# untitled.net
KiCad netlist of a schematic drawn in EAGLE
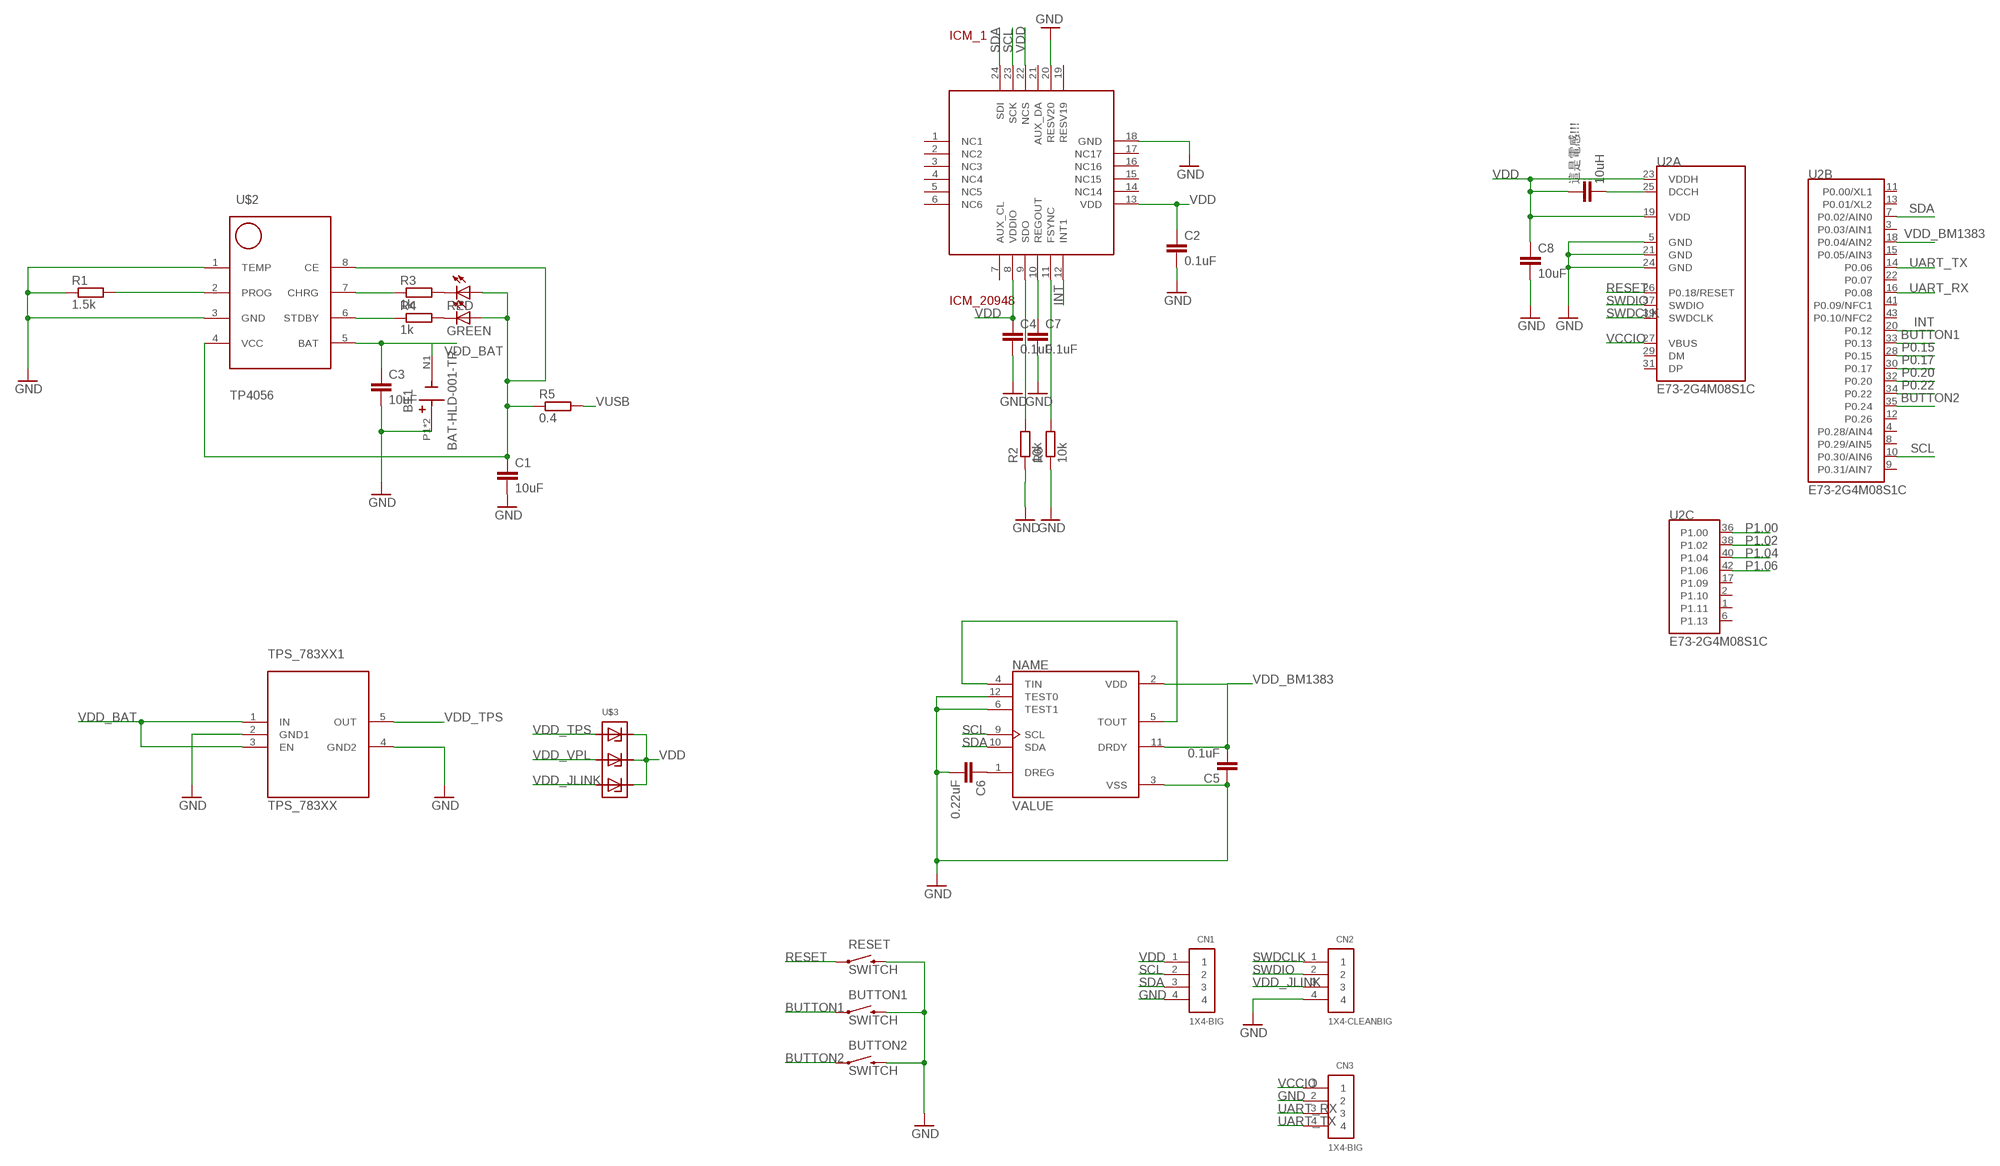
[diagram p0: schematic, sheet 1]

(export (version "E")
  (design (tool "Eeschema 10.0.6"))
  (components
    (comp (ref "BT1")
      (value "BAT-HLD-001-TR")
      (footprint "eagle-import:BAT_BAT-HLD-001-TR")
      (fields (field (name "MF") "Linx"))
      (libsource (lib "eagle-import") (part "BAT-HLD-001-TR"))
    )
    (comp (ref "BUTTON1")
      (value "SWITCH")
      (footprint "eagle-import:SWITCH_2PIN")
      (libsource (lib "eagle-import") (part "SWITCH"))
    )
    (comp (ref "BUTTON2")
      (value "SWITCH")
      (footprint "eagle-import:SWITCH_2PIN")
      (libsource (lib "eagle-import") (part "SWITCH"))
    )
    (comp (ref "C1")
      (value "10uF")
      (footprint "eagle-import:C0805")
      (libsource (lib "eagle-import") (part "C-EUC0805"))
    )
    (comp (ref "C2")
      (value "0.1uF")
      (footprint "eagle-import:C0805")
      (libsource (lib "eagle-import") (part "C-EUC0805"))
    )
    (comp (ref "C3")
      (value "10uF")
      (footprint "eagle-import:C0805")
      (libsource (lib "eagle-import") (part "C-EUC0805"))
    )
    (comp (ref "C4")
      (value "0.1uF")
      (footprint "eagle-import:C0805")
      (libsource (lib "eagle-import") (part "C-EUC0805"))
    )
    (comp (ref "C5")
      (value "0.1uF")
      (footprint "eagle-import:C0805")
      (libsource (lib "eagle-import") (part "C-EUC0805"))
    )
    (comp (ref "C6")
      (value "0.22uF")
      (footprint "eagle-import:C0805")
      (libsource (lib "eagle-import") (part "C-EUC0805"))
    )
    (comp (ref "C7")
      (value "0.1uF")
      (footprint "eagle-import:C0805")
      (libsource (lib "eagle-import") (part "C-EUC0805"))
    )
    (comp (ref "C8")
      (value "10uF")
      (footprint "eagle-import:C0805")
      (libsource (lib "eagle-import") (part "C-EUC0805"))
    )
    (comp (ref "CN1")
      (value "1X4-BIG")
      (footprint "eagle-import:1X04-BIG")
      (libsource (lib "eagle-import") (part "1X4-BIG"))
    )
    (comp (ref "CN2")
      (value "1X4-CLEANBIG")
      (footprint "eagle-import:1X04-CLEANBIG")
      (libsource (lib "eagle-import") (part "1X4-CLEANBIG"))
    )
    (comp (ref "CN3")
      (value "1X4-BIG")
      (footprint "eagle-import:1X04-BIG")
      (libsource (lib "eagle-import") (part "1X4-BIG"))
    )
    (comp (ref "GREEN")
      (value "LED_E")
      (footprint "eagle-import:LED_1206")
      (libsource (lib "eagle-import") (part "LED_E"))
    )
    (comp (ref "ICM_1")
      (value "ICM_20948")
      (footprint "eagle-import:QFN40P300X300X105-25N")
      (libsource (lib "eagle-import") (part "ICM_20948"))
    )
    (comp (ref "R1")
      (value "1.5k")
      (footprint "eagle-import:R0805")
      (libsource (lib "eagle-import") (part "R"))
    )
    (comp (ref "R2")
      (value "10k")
      (footprint "eagle-import:R0805")
      (libsource (lib "eagle-import") (part "R"))
    )
    (comp (ref "R3")
      (value "1k")
      (footprint "eagle-import:R0805")
      (libsource (lib "eagle-import") (part "R"))
    )
    (comp (ref "R4")
      (value "1k")
      (footprint "eagle-import:R0805")
      (libsource (lib "eagle-import") (part "R"))
    )
    (comp (ref "R5")
      (value "0.4")
      (footprint "eagle-import:R0805")
      (libsource (lib "eagle-import") (part "R"))
    )
    (comp (ref "R6")
      (value "10k")
      (footprint "eagle-import:R0805")
      (libsource (lib "eagle-import") (part "R"))
    )
    (comp (ref "RED")
      (value "LED_E")
      (footprint "eagle-import:LED_1206")
      (libsource (lib "eagle-import") (part "LED_E"))
    )
    (comp (ref "RESET")
      (value "SWITCH")
      (footprint "eagle-import:SWITCH_2PIN")
      (libsource (lib "eagle-import") (part "SWITCH"))
    )
    (comp (ref "TPS_783XX1")
      (value "TPS_783XX")
      (footprint "eagle-import:SOT65P280X145-5N")
      (libsource (lib "eagle-import") (part "TPS_783XX"))
    )
    (comp (ref "U$2")
      (value "TP4056")
      (footprint "eagle-import:SOP8")
      (libsource (lib "eagle-import") (part "TP4056"))
    )
    (comp (ref "U$3")
      (value "SD103ATW")
      (footprint "eagle-import:SOT363")
      (libsource (lib "eagle-import") (part "SD103ATW"))
    )
    (comp (ref "U1")
      (value "BM1383AGLV-ZE2")
      (footprint "eagle-import:PQFN55P250X250X100-12N")
      (fields (field (name "MF") "Rohm"))
      (libsource (lib "eagle-import") (part "BM1383AGLV-ZE2"))
    )
    (comp (ref "U2")
      (value "E73-2G4M08S1C")
      (footprint "eagle-import:E73-2G4M08S1C")
      (libsource (lib "eagle-import") (part "E73-2G4M08S1C"))
    )
    (comp (ref "這是電感!!!")
      (value "10uH")
      (footprint "eagle-import:C0805")
      (libsource (lib "eagle-import") (part "C-EUC0805"))
    )
  )
  (nets
    (net (code "1") (name "/BUTTON1") (class "Default")
      (node (ref "BUTTON1") (pin "1") (pinfunction "1_1") (pintype "passive"))
      (node (ref "U2") (pin "33") (pinfunction "P0.13_33") (pintype "bidirectional"))
    )
    (net (code "2") (name "/BUTTON2") (class "Default")
      (node (ref "BUTTON2") (pin "1") (pinfunction "1_1") (pintype "passive"))
      (node (ref "U2") (pin "35") (pinfunction "P0.24_35") (pintype "bidirectional"))
    )
    (net (code "3") (name "/INT") (class "Default")
      (node (ref "ICM_1") (pin "12") (pinfunction "INT1_12") (pintype "bidirectional"))
      (node (ref "U2") (pin "20") (pinfunction "P0.12_20") (pintype "bidirectional"))
    )
    (net (code "4") (name "/P0.15") (class "Default")
      (node (ref "U2") (pin "28") (pinfunction "P0.15_28") (pintype "bidirectional"))
    )
    (net (code "5") (name "/P0.17") (class "Default")
      (node (ref "U2") (pin "30") (pinfunction "P0.17_30") (pintype "bidirectional"))
    )
    (net (code "6") (name "/P0.20") (class "Default")
      (node (ref "U2") (pin "32") (pinfunction "P0.20_32") (pintype "bidirectional"))
    )
    (net (code "7") (name "/P0.22") (class "Default")
      (node (ref "U2") (pin "34") (pinfunction "P0.22_34") (pintype "bidirectional"))
    )
    (net (code "8") (name "/P1.00") (class "Default")
      (node (ref "U2") (pin "36") (pinfunction "P1.00_36") (pintype "bidirectional"))
    )
    (net (code "9") (name "/P1.02") (class "Default")
      (node (ref "U2") (pin "38") (pinfunction "P1.02_38") (pintype "bidirectional"))
    )
    (net (code "10") (name "/P1.04") (class "Default")
      (node (ref "U2") (pin "40") (pinfunction "P1.04_40") (pintype "bidirectional"))
    )
    (net (code "11") (name "/P1.06") (class "Default")
      (node (ref "U2") (pin "42") (pinfunction "P1.06_42") (pintype "bidirectional"))
    )
    (net (code "12") (name "/RESET") (class "Default")
      (node (ref "RESET") (pin "1") (pinfunction "1_1") (pintype "passive"))
      (node (ref "U2") (pin "26") (pinfunction "P0.18/RESET_26") (pintype "bidirectional"))
    )
    (net (code "13") (name "/SCL") (class "Default")
      (node (ref "CN1") (pin "2") (pinfunction "2_2") (pintype "bidirectional"))
      (node (ref "ICM_1") (pin "23") (pinfunction "SCK_23") (pintype "bidirectional"))
      (node (ref "U1") (pin "9") (pinfunction "SCL_9") (pintype "input"))
      (node (ref "U2") (pin "10") (pinfunction "P0.30/AIN6_10") (pintype "bidirectional"))
    )
    (net (code "14") (name "/SDA") (class "Default")
      (node (ref "CN1") (pin "3") (pinfunction "3_3") (pintype "bidirectional"))
      (node (ref "ICM_1") (pin "24") (pinfunction "SDI_24") (pintype "bidirectional"))
      (node (ref "U1") (pin "10") (pinfunction "SDA_10") (pintype "bidirectional"))
      (node (ref "U2") (pin "7") (pinfunction "P0.02/AIN0_7") (pintype "bidirectional"))
    )
    (net (code "15") (name "/SWDCLK") (class "Default")
      (node (ref "CN2") (pin "1") (pinfunction "1_1") (pintype "bidirectional"))
      (node (ref "U2") (pin "39") (pinfunction "SWDCLK_39") (pintype "bidirectional"))
    )
    (net (code "16") (name "/SWDIO") (class "Default")
      (node (ref "CN2") (pin "2") (pinfunction "2_2") (pintype "bidirectional"))
      (node (ref "U2") (pin "37") (pinfunction "SWDIO_37") (pintype "bidirectional"))
    )
    (net (code "17") (name "/UART_RX") (class "Default")
      (node (ref "CN3") (pin "3") (pinfunction "3_3") (pintype "bidirectional"))
      (node (ref "U2") (pin "16") (pinfunction "P0.08_16") (pintype "bidirectional"))
    )
    (net (code "18") (name "/UART_TX") (class "Default")
      (node (ref "CN3") (pin "4") (pinfunction "4_4") (pintype "bidirectional"))
      (node (ref "U2") (pin "14") (pinfunction "P0.06_14") (pintype "bidirectional"))
    )
    (net (code "19") (name "/VCCIO") (class "Default")
      (node (ref "CN3") (pin "1") (pinfunction "1_1") (pintype "bidirectional"))
      (node (ref "U2") (pin "27") (pinfunction "VBUS_27") (pintype "bidirectional"))
    )
    (net (code "20") (name "/VDD") (class "Default")
      (node (ref "C2") (pin "1") (pinfunction "1_1") (pintype "passive"))
      (node (ref "C4") (pin "1") (pinfunction "1_1") (pintype "passive"))
      (node (ref "C8") (pin "1") (pinfunction "1_1") (pintype "passive"))
      (node (ref "CN1") (pin "1") (pinfunction "1_1") (pintype "bidirectional"))
      (node (ref "ICM_1") (pin "13") (pinfunction "VDD_13") (pintype "bidirectional"))
      (node (ref "ICM_1") (pin "22") (pinfunction "NCS_22") (pintype "bidirectional"))
      (node (ref "ICM_1") (pin "8") (pinfunction "VDDIO_8") (pintype "bidirectional"))
      (node (ref "U$3") (pin "2") (pinfunction "2_2") (pintype "bidirectional"))
      (node (ref "U$3") (pin "4") (pinfunction "4_4") (pintype "bidirectional"))
      (node (ref "U$3") (pin "6") (pinfunction "6_6") (pintype "bidirectional"))
      (node (ref "U2") (pin "19") (pinfunction "VDD_19") (pintype "bidirectional"))
      (node (ref "U2") (pin "23") (pinfunction "VDDH_23") (pintype "bidirectional"))
      (node (ref "這是電感!!!") (pin "1") (pinfunction "1_1") (pintype "passive"))
    )
    (net (code "21") (name "/VDD_BAT") (class "Default")
      (node (ref "BT1") (pin "N1") (pinfunction "-_N1") (pintype "passive"))
      (node (ref "C3") (pin "1") (pinfunction "1_1") (pintype "passive"))
      (node (ref "TPS_783XX1") (pin "1") (pinfunction "IN_1") (pintype "bidirectional"))
      (node (ref "TPS_783XX1") (pin "3") (pinfunction "EN_3") (pintype "bidirectional"))
      (node (ref "U$2") (pin "5") (pinfunction "BAT_5") (pintype "bidirectional"))
    )
    (net (code "22") (name "/VDD_BM1383") (class "Default")
      (node (ref "C5") (pin "2") (pinfunction "2_2") (pintype "passive"))
      (node (ref "U1") (pin "11") (pinfunction "DRDY_11") (pintype "output"))
      (node (ref "U1") (pin "2") (pinfunction "VDD_2") (pintype "power_in"))
      (node (ref "U2") (pin "18") (pinfunction "P0.04/AIN2_18") (pintype "bidirectional"))
    )
    (net (code "23") (name "/VDD_JLINK") (class "Default")
      (node (ref "CN2") (pin "3") (pinfunction "3_3") (pintype "bidirectional"))
      (node (ref "U$3") (pin "5") (pinfunction "5_5") (pintype "bidirectional"))
    )
    (net (code "24") (name "/VDD_TPS") (class "Default")
      (node (ref "TPS_783XX1") (pin "5") (pinfunction "OUT_5") (pintype "bidirectional"))
      (node (ref "U$3") (pin "1") (pinfunction "1_1") (pintype "bidirectional"))
    )
    (net (code "25") (name "/VDD_VPL") (class "Default")
      (node (ref "U$3") (pin "3") (pinfunction "3_3") (pintype "bidirectional"))
    )
    (net (code "26") (name "/VUSB") (class "Default")
      (node (ref "R5") (pin "2") (pinfunction "2_2") (pintype "passive"))
    )
    (net (code "27") (name "GND") (class "Default")
      (node (ref "BT1") (pin "P1") (pinfunction "+_P1") (pintype "passive"))
      (node (ref "BT1") (pin "P2") (pinfunction "+_P2") (pintype "passive"))
      (node (ref "BUTTON1") (pin "2") (pinfunction "2_2") (pintype "passive"))
      (node (ref "BUTTON2") (pin "2") (pinfunction "2_2") (pintype "passive"))
      (node (ref "C1") (pin "2") (pinfunction "2_2") (pintype "passive"))
      (node (ref "C2") (pin "2") (pinfunction "2_2") (pintype "passive"))
      (node (ref "C3") (pin "2") (pinfunction "2_2") (pintype "passive"))
      (node (ref "C4") (pin "2") (pinfunction "2_2") (pintype "passive"))
      (node (ref "C5") (pin "1") (pinfunction "1_1") (pintype "passive"))
      (node (ref "C6") (pin "2") (pinfunction "2_2") (pintype "passive"))
      (node (ref "C7") (pin "2") (pinfunction "2_2") (pintype "passive"))
      (node (ref "C8") (pin "2") (pinfunction "2_2") (pintype "passive"))
      (node (ref "CN1") (pin "4") (pinfunction "4_4") (pintype "bidirectional"))
      (node (ref "CN2") (pin "4") (pinfunction "4_4") (pintype "bidirectional"))
      (node (ref "CN3") (pin "2") (pinfunction "2_2") (pintype "bidirectional"))
      (node (ref "ICM_1") (pin "18") (pinfunction "GND_18") (pintype "bidirectional"))
      (node (ref "ICM_1") (pin "20") (pinfunction "RESV20_20") (pintype "bidirectional"))
      (node (ref "R1") (pin "1") (pinfunction "1_1") (pintype "passive"))
      (node (ref "R2") (pin "1") (pinfunction "1_1") (pintype "passive"))
      (node (ref "R6") (pin "1") (pinfunction "1_1") (pintype "passive"))
      (node (ref "RESET") (pin "2") (pinfunction "2_2") (pintype "passive"))
      (node (ref "TPS_783XX1") (pin "2") (pinfunction "GND1_2") (pintype "bidirectional"))
      (node (ref "TPS_783XX1") (pin "4") (pinfunction "GND2_4") (pintype "bidirectional"))
      (node (ref "U$2") (pin "1") (pinfunction "TEMP_1") (pintype "bidirectional"))
      (node (ref "U$2") (pin "3") (pinfunction "GND_3") (pintype "bidirectional"))
      (node (ref "U1") (pin "12") (pinfunction "TEST0_12") (pintype "input"))
      (node (ref "U1") (pin "3") (pinfunction "VSS_3") (pintype "power_in"))
      (node (ref "U1") (pin "6") (pinfunction "TEST1_6") (pintype "input"))
      (node (ref "U2") (pin "21") (pinfunction "GND_21") (pintype "bidirectional"))
      (node (ref "U2") (pin "24") (pinfunction "GND_24") (pintype "bidirectional"))
      (node (ref "U2") (pin "5") (pinfunction "GND_5") (pintype "bidirectional"))
    )
    (net (code "28") (name "Net-(GREEN-PadC)") (class "Default")
      (node (ref "GREEN") (pin "C") (pinfunction "C_C") (pintype "passive"))
      (node (ref "R4") (pin "2") (pinfunction "2_2") (pintype "passive"))
    )
    (net (code "29") (name "Net-(ICM_1-FSYNC)") (class "Default")
      (node (ref "ICM_1") (pin "11") (pinfunction "FSYNC_11") (pintype "bidirectional"))
      (node (ref "R6") (pin "2") (pinfunction "2_2") (pintype "passive"))
    )
    (net (code "30") (name "Net-(ICM_1-REGOUT)") (class "Default")
      (node (ref "C7") (pin "1") (pinfunction "1_1") (pintype "passive"))
      (node (ref "ICM_1") (pin "10") (pinfunction "REGOUT_10") (pintype "bidirectional"))
    )
    (net (code "31") (name "Net-(ICM_1-SDO)") (class "Default")
      (node (ref "ICM_1") (pin "9") (pinfunction "SDO_9") (pintype "bidirectional"))
      (node (ref "R2") (pin "2") (pinfunction "2_2") (pintype "passive"))
    )
    (net (code "32") (name "Net-(R3-Pad2)") (class "Default")
      (node (ref "R3") (pin "2") (pinfunction "2_2") (pintype "passive"))
      (node (ref "RED") (pin "C") (pinfunction "C_C") (pintype "passive"))
    )
    (net (code "33") (name "Net-(U$2-CE)") (class "Default")
      (node (ref "C1") (pin "1") (pinfunction "1_1") (pintype "passive"))
      (node (ref "GREEN") (pin "A") (pinfunction "A_A") (pintype "passive"))
      (node (ref "R5") (pin "1") (pinfunction "1_1") (pintype "passive"))
      (node (ref "RED") (pin "A") (pinfunction "A_A") (pintype "passive"))
      (node (ref "U$2") (pin "4") (pinfunction "VCC_4") (pintype "bidirectional"))
      (node (ref "U$2") (pin "8") (pinfunction "CE_8") (pintype "bidirectional"))
    )
    (net (code "34") (name "Net-(U$2-CHRG)") (class "Default")
      (node (ref "R3") (pin "1") (pinfunction "1_1") (pintype "passive"))
      (node (ref "U$2") (pin "7") (pinfunction "CHRG_7") (pintype "bidirectional"))
    )
    (net (code "35") (name "Net-(U$2-PROG)") (class "Default")
      (node (ref "R1") (pin "2") (pinfunction "2_2") (pintype "passive"))
      (node (ref "U$2") (pin "2") (pinfunction "PROG_2") (pintype "bidirectional"))
    )
    (net (code "36") (name "Net-(U$2-STDBY)") (class "Default")
      (node (ref "R4") (pin "1") (pinfunction "1_1") (pintype "passive"))
      (node (ref "U$2") (pin "6") (pinfunction "STDBY_6") (pintype "bidirectional"))
    )
    (net (code "37") (name "Net-(U1-DREG)") (class "Default")
      (node (ref "C6") (pin "1") (pinfunction "1_1") (pintype "passive"))
      (node (ref "U1") (pin "1") (pinfunction "DREG_1") (pintype "passive"))
    )
    (net (code "38") (name "Net-(U1-TIN)") (class "Default")
      (node (ref "U1") (pin "4") (pinfunction "TIN_4") (pintype "input"))
      (node (ref "U1") (pin "5") (pinfunction "TOUT_5") (pintype "output"))
    )
    (net (code "39") (name "Net-(U2A-DCCH)") (class "Default")
      (node (ref "U2") (pin "25") (pinfunction "DCCH_25") (pintype "bidirectional"))
      (node (ref "這是電感!!!") (pin "2") (pinfunction "2_2") (pintype "passive"))
    )
    (net (code "40") (name "unconnected-(ICM_1-AUX_CL-Pad7)") (class "Default")
      (node (ref "ICM_1") (pin "7") (pinfunction "AUX_CL_7") (pintype "bidirectional"))
    )
    (net (code "41") (name "unconnected-(ICM_1-AUX_DA-Pad21)") (class "Default")
      (node (ref "ICM_1") (pin "21") (pinfunction "AUX_DA_21") (pintype "bidirectional"))
    )
    (net (code "42") (name "unconnected-(ICM_1-NC1-Pad1)") (class "Default")
      (node (ref "ICM_1") (pin "1") (pinfunction "NC1_1") (pintype "bidirectional"))
    )
    (net (code "43") (name "unconnected-(ICM_1-NC2-Pad2)") (class "Default")
      (node (ref "ICM_1") (pin "2") (pinfunction "NC2_2") (pintype "bidirectional"))
    )
    (net (code "44") (name "unconnected-(ICM_1-NC3-Pad3)") (class "Default")
      (node (ref "ICM_1") (pin "3") (pinfunction "NC3_3") (pintype "bidirectional"))
    )
    (net (code "45") (name "unconnected-(ICM_1-NC4-Pad4)") (class "Default")
      (node (ref "ICM_1") (pin "4") (pinfunction "NC4_4") (pintype "bidirectional"))
    )
    (net (code "46") (name "unconnected-(ICM_1-NC5-Pad5)") (class "Default")
      (node (ref "ICM_1") (pin "5") (pinfunction "NC5_5") (pintype "bidirectional"))
    )
    (net (code "47") (name "unconnected-(ICM_1-NC6-Pad6)") (class "Default")
      (node (ref "ICM_1") (pin "6") (pinfunction "NC6_6") (pintype "bidirectional"))
    )
    (net (code "48") (name "unconnected-(ICM_1-NC14-Pad14)") (class "Default")
      (node (ref "ICM_1") (pin "14") (pinfunction "NC14_14") (pintype "bidirectional"))
    )
    (net (code "49") (name "unconnected-(ICM_1-NC15-Pad15)") (class "Default")
      (node (ref "ICM_1") (pin "15") (pinfunction "NC15_15") (pintype "bidirectional"))
    )
    (net (code "50") (name "unconnected-(ICM_1-NC16-Pad16)") (class "Default")
      (node (ref "ICM_1") (pin "16") (pinfunction "NC16_16") (pintype "bidirectional"))
    )
    (net (code "51") (name "unconnected-(ICM_1-NC17-Pad17)") (class "Default")
      (node (ref "ICM_1") (pin "17") (pinfunction "NC17_17") (pintype "bidirectional"))
    )
    (net (code "52") (name "unconnected-(ICM_1-RESV19-Pad19)") (class "Default")
      (node (ref "ICM_1") (pin "19") (pinfunction "RESV19_19") (pintype "bidirectional"))
    )
    (net (code "53") (name "unconnected-(U2A-DM-Pad29)") (class "Default")
      (node (ref "U2") (pin "29") (pinfunction "DM_29") (pintype "bidirectional"))
    )
    (net (code "54") (name "unconnected-(U2A-DP-Pad31)") (class "Default")
      (node (ref "U2") (pin "31") (pinfunction "DP_31") (pintype "bidirectional"))
    )
    (net (code "55") (name "unconnected-(U2B-P0.00{slash}XL1-Pad11)") (class "Default")
      (node (ref "U2") (pin "11") (pinfunction "P0.00/XL1_11") (pintype "bidirectional"))
    )
    (net (code "56") (name "unconnected-(U2B-P0.01{slash}XL2-Pad13)") (class "Default")
      (node (ref "U2") (pin "13") (pinfunction "P0.01/XL2_13") (pintype "bidirectional"))
    )
    (net (code "57") (name "unconnected-(U2B-P0.03{slash}AIN1-Pad3)") (class "Default")
      (node (ref "U2") (pin "3") (pinfunction "P0.03/AIN1_3") (pintype "bidirectional"))
    )
    (net (code "58") (name "unconnected-(U2B-P0.05{slash}AIN3-Pad15)") (class "Default")
      (node (ref "U2") (pin "15") (pinfunction "P0.05/AIN3_15") (pintype "bidirectional"))
    )
    (net (code "59") (name "unconnected-(U2B-P0.07-Pad22)") (class "Default")
      (node (ref "U2") (pin "22") (pinfunction "P0.07_22") (pintype "bidirectional"))
    )
    (net (code "60") (name "unconnected-(U2B-P0.09{slash}NFC1-Pad41)") (class "Default")
      (node (ref "U2") (pin "41") (pinfunction "P0.09/NFC1_41") (pintype "bidirectional"))
    )
    (net (code "61") (name "unconnected-(U2B-P0.10{slash}NFC2-Pad43)") (class "Default")
      (node (ref "U2") (pin "43") (pinfunction "P0.10/NFC2_43") (pintype "bidirectional"))
    )
    (net (code "62") (name "unconnected-(U2B-P0.26-Pad12)") (class "Default")
      (node (ref "U2") (pin "12") (pinfunction "P0.26_12") (pintype "bidirectional"))
    )
    (net (code "63") (name "unconnected-(U2B-P0.28{slash}AIN4-Pad4)") (class "Default")
      (node (ref "U2") (pin "4") (pinfunction "P0.28/AIN4_4") (pintype "bidirectional"))
    )
    (net (code "64") (name "unconnected-(U2B-P0.29{slash}AIN5-Pad8)") (class "Default")
      (node (ref "U2") (pin "8") (pinfunction "P0.29/AIN5_8") (pintype "bidirectional"))
    )
    (net (code "65") (name "unconnected-(U2B-P0.31{slash}AIN7-Pad9)") (class "Default")
      (node (ref "U2") (pin "9") (pinfunction "P0.31/AIN7_9") (pintype "bidirectional"))
    )
    (net (code "66") (name "unconnected-(U2C-P1.09-Pad17)") (class "Default")
      (node (ref "U2") (pin "17") (pinfunction "P1.09_17") (pintype "bidirectional"))
    )
    (net (code "67") (name "unconnected-(U2C-P1.10-Pad2)") (class "Default")
      (node (ref "U2") (pin "2") (pinfunction "P1.10_2") (pintype "bidirectional"))
    )
    (net (code "68") (name "unconnected-(U2C-P1.11-Pad1)") (class "Default")
      (node (ref "U2") (pin "1") (pinfunction "P1.11_1") (pintype "bidirectional"))
    )
    (net (code "69") (name "unconnected-(U2C-P1.13-Pad6)") (class "Default")
      (node (ref "U2") (pin "6") (pinfunction "P1.13_6") (pintype "bidirectional"))
    )
  )
)
